# R181X.net
KiCad netlist of a schematic drawn in EAGLE
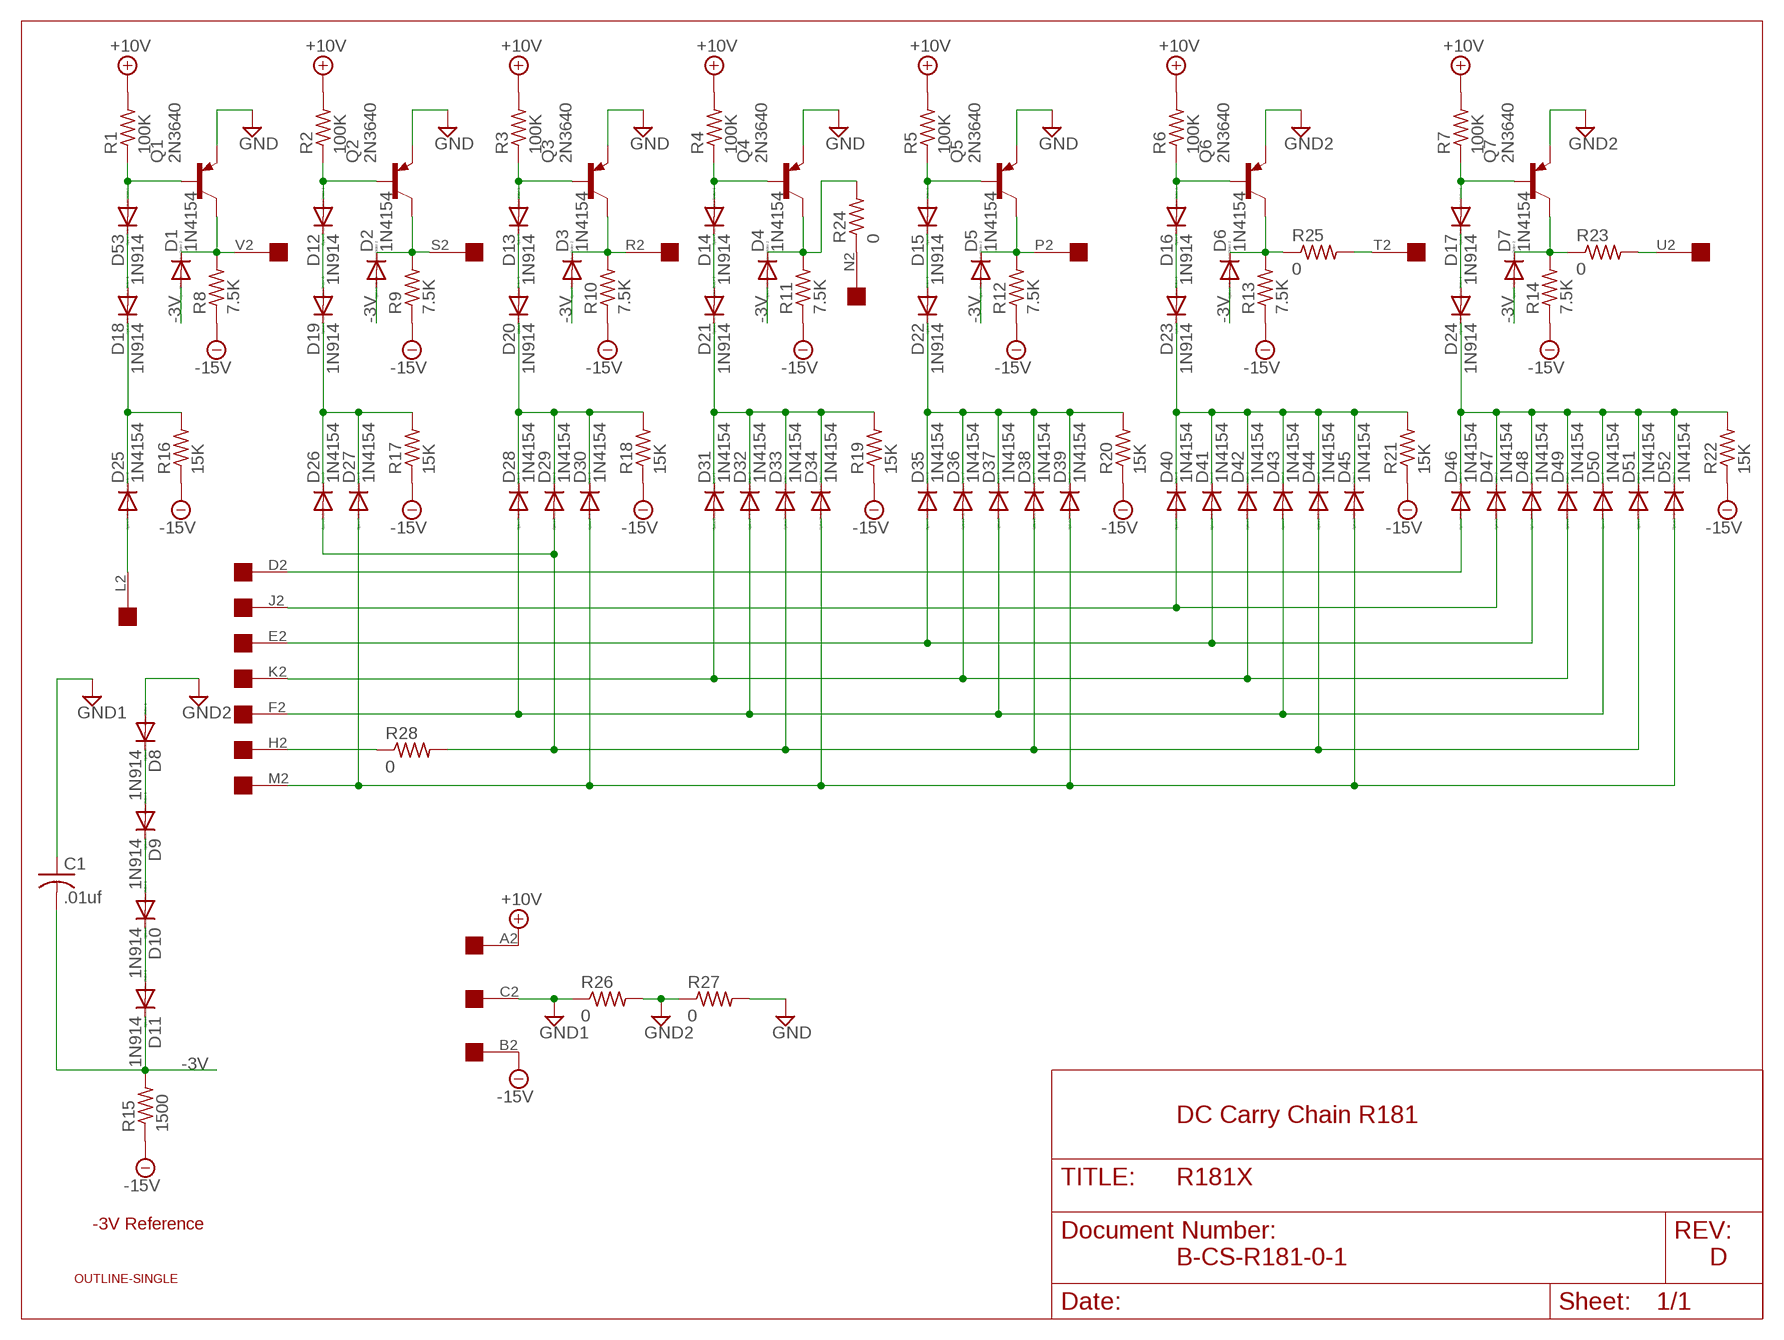
[diagram p0: schematic, sheet 1]

(export (version "E")
  (design (tool "Eeschema 10.0.6"))
  (components
    (comp (ref "C1")
      (value ".01uf")
      (footprint "eagle-import:C050-025X075")
      (libsource (lib "eagle-import") (part "C-US050-025X075"))
    )
    (comp (ref "D1")
      (value "1N4154")
      (footprint "eagle-import:DO35-10")
      (libsource (lib "eagle-import") (part "1N4148DO35-10"))
    )
    (comp (ref "D2")
      (value "1N4154")
      (footprint "eagle-import:DO35-10")
      (libsource (lib "eagle-import") (part "1N4148DO35-10"))
    )
    (comp (ref "D3")
      (value "1N4154")
      (footprint "eagle-import:DO35-10")
      (libsource (lib "eagle-import") (part "1N4148DO35-10"))
    )
    (comp (ref "D4")
      (value "1N4154")
      (footprint "eagle-import:DO35-10")
      (libsource (lib "eagle-import") (part "1N4148DO35-10"))
    )
    (comp (ref "D5")
      (value "1N4154")
      (footprint "eagle-import:DO35-10")
      (libsource (lib "eagle-import") (part "1N4148DO35-10"))
    )
    (comp (ref "D6")
      (value "1N4154")
      (footprint "eagle-import:DO35-10")
      (libsource (lib "eagle-import") (part "1N4148DO35-10"))
    )
    (comp (ref "D7")
      (value "1N4154")
      (footprint "eagle-import:DO35-10")
      (libsource (lib "eagle-import") (part "1N4148DO35-10"))
    )
    (comp (ref "D8")
      (value "1N914")
      (footprint "eagle-import:DO35-10")
      (libsource (lib "eagle-import") (part "1N4148DO35-10"))
    )
    (comp (ref "D9")
      (value "1N914")
      (footprint "eagle-import:DO35-10")
      (libsource (lib "eagle-import") (part "1N4148DO35-10"))
    )
    (comp (ref "D10")
      (value "1N914")
      (footprint "eagle-import:DO35-10")
      (libsource (lib "eagle-import") (part "1N4148DO35-10"))
    )
    (comp (ref "D11")
      (value "1N914")
      (footprint "eagle-import:DO35-10")
      (libsource (lib "eagle-import") (part "1N4148DO35-10"))
    )
    (comp (ref "D12")
      (value "1N914")
      (footprint "eagle-import:DO35-10")
      (libsource (lib "eagle-import") (part "1N4148DO35-10"))
    )
    (comp (ref "D13")
      (value "1N914")
      (footprint "eagle-import:DO35-10")
      (libsource (lib "eagle-import") (part "1N4148DO35-10"))
    )
    (comp (ref "D14")
      (value "1N914")
      (footprint "eagle-import:DO35-10")
      (libsource (lib "eagle-import") (part "1N4148DO35-10"))
    )
    (comp (ref "D15")
      (value "1N914")
      (footprint "eagle-import:DO35-10")
      (libsource (lib "eagle-import") (part "1N4148DO35-10"))
    )
    (comp (ref "D16")
      (value "1N914")
      (footprint "eagle-import:DO35-10")
      (libsource (lib "eagle-import") (part "1N4148DO35-10"))
    )
    (comp (ref "D17")
      (value "1N914")
      (footprint "eagle-import:DO35-10")
      (libsource (lib "eagle-import") (part "1N4148DO35-10"))
    )
    (comp (ref "D18")
      (value "1N914")
      (footprint "eagle-import:DO35-10")
      (libsource (lib "eagle-import") (part "1N4148DO35-10"))
    )
    (comp (ref "D19")
      (value "1N914")
      (footprint "eagle-import:DO35-10")
      (libsource (lib "eagle-import") (part "1N4148DO35-10"))
    )
    (comp (ref "D20")
      (value "1N914")
      (footprint "eagle-import:DO35-10")
      (libsource (lib "eagle-import") (part "1N4148DO35-10"))
    )
    (comp (ref "D21")
      (value "1N914")
      (footprint "eagle-import:DO35-10")
      (libsource (lib "eagle-import") (part "1N4148DO35-10"))
    )
    (comp (ref "D22")
      (value "1N914")
      (footprint "eagle-import:DO35-10")
      (libsource (lib "eagle-import") (part "1N4148DO35-10"))
    )
    (comp (ref "D23")
      (value "1N914")
      (footprint "eagle-import:DO35-10")
      (libsource (lib "eagle-import") (part "1N4148DO35-10"))
    )
    (comp (ref "D24")
      (value "1N914")
      (footprint "eagle-import:DO35-10")
      (libsource (lib "eagle-import") (part "1N4148DO35-10"))
    )
    (comp (ref "D25")
      (value "1N4154")
      (footprint "eagle-import:DO35-10")
      (libsource (lib "eagle-import") (part "1N4148DO35-10"))
    )
    (comp (ref "D26")
      (value "1N4154")
      (footprint "eagle-import:DO35-10")
      (libsource (lib "eagle-import") (part "1N4148DO35-10"))
    )
    (comp (ref "D27")
      (value "1N4154")
      (footprint "eagle-import:DO35-10")
      (libsource (lib "eagle-import") (part "1N4148DO35-10"))
    )
    (comp (ref "D28")
      (value "1N4154")
      (footprint "eagle-import:DO35-10")
      (libsource (lib "eagle-import") (part "1N4148DO35-10"))
    )
    (comp (ref "D29")
      (value "1N4154")
      (footprint "eagle-import:DO35-10")
      (libsource (lib "eagle-import") (part "1N4148DO35-10"))
    )
    (comp (ref "D30")
      (value "1N4154")
      (footprint "eagle-import:DO35-10")
      (libsource (lib "eagle-import") (part "1N4148DO35-10"))
    )
    (comp (ref "D31")
      (value "1N4154")
      (footprint "eagle-import:DO35-10")
      (libsource (lib "eagle-import") (part "1N4148DO35-10"))
    )
    (comp (ref "D32")
      (value "1N4154")
      (footprint "eagle-import:DO35-10")
      (libsource (lib "eagle-import") (part "1N4148DO35-10"))
    )
    (comp (ref "D33")
      (value "1N4154")
      (footprint "eagle-import:DO35-10")
      (libsource (lib "eagle-import") (part "1N4148DO35-10"))
    )
    (comp (ref "D34")
      (value "1N4154")
      (footprint "eagle-import:DO35-10")
      (libsource (lib "eagle-import") (part "1N4148DO35-10"))
    )
    (comp (ref "D35")
      (value "1N4154")
      (footprint "eagle-import:DO35-10")
      (libsource (lib "eagle-import") (part "1N4148DO35-10"))
    )
    (comp (ref "D36")
      (value "1N4154")
      (footprint "eagle-import:DO35-10")
      (libsource (lib "eagle-import") (part "1N4148DO35-10"))
    )
    (comp (ref "D37")
      (value "1N4154")
      (footprint "eagle-import:DO35-10")
      (libsource (lib "eagle-import") (part "1N4148DO35-10"))
    )
    (comp (ref "D38")
      (value "1N4154")
      (footprint "eagle-import:DO35-10")
      (libsource (lib "eagle-import") (part "1N4148DO35-10"))
    )
    (comp (ref "D39")
      (value "1N4154")
      (footprint "eagle-import:DO35-10")
      (libsource (lib "eagle-import") (part "1N4148DO35-10"))
    )
    (comp (ref "D40")
      (value "1N4154")
      (footprint "eagle-import:DO35-10")
      (libsource (lib "eagle-import") (part "1N4148DO35-10"))
    )
    (comp (ref "D41")
      (value "1N4154")
      (footprint "eagle-import:DO35-10")
      (libsource (lib "eagle-import") (part "1N4148DO35-10"))
    )
    (comp (ref "D42")
      (value "1N4154")
      (footprint "eagle-import:DO35-10")
      (libsource (lib "eagle-import") (part "1N4148DO35-10"))
    )
    (comp (ref "D43")
      (value "1N4154")
      (footprint "eagle-import:DO35-10")
      (libsource (lib "eagle-import") (part "1N4148DO35-10"))
    )
    (comp (ref "D44")
      (value "1N4154")
      (footprint "eagle-import:DO35-10")
      (libsource (lib "eagle-import") (part "1N4148DO35-10"))
    )
    (comp (ref "D45")
      (value "1N4154")
      (footprint "eagle-import:DO35-10")
      (libsource (lib "eagle-import") (part "1N4148DO35-10"))
    )
    (comp (ref "D46")
      (value "1N4154")
      (footprint "eagle-import:DO35-10")
      (libsource (lib "eagle-import") (part "1N4148DO35-10"))
    )
    (comp (ref "D47")
      (value "1N4154")
      (footprint "eagle-import:DO35-10")
      (libsource (lib "eagle-import") (part "1N4148DO35-10"))
    )
    (comp (ref "D48")
      (value "1N4154")
      (footprint "eagle-import:DO35-10")
      (libsource (lib "eagle-import") (part "1N4148DO35-10"))
    )
    (comp (ref "D49")
      (value "1N4154")
      (footprint "eagle-import:DO35-10")
      (libsource (lib "eagle-import") (part "1N4148DO35-10"))
    )
    (comp (ref "D50")
      (value "1N4154")
      (footprint "eagle-import:DO35-10")
      (libsource (lib "eagle-import") (part "1N4148DO35-10"))
    )
    (comp (ref "D51")
      (value "1N4154")
      (footprint "eagle-import:DO35-10")
      (libsource (lib "eagle-import") (part "1N4148DO35-10"))
    )
    (comp (ref "D52")
      (value "1N4154")
      (footprint "eagle-import:DO35-10")
      (libsource (lib "eagle-import") (part "1N4148DO35-10"))
    )
    (comp (ref "D53")
      (value "1N914")
      (footprint "eagle-import:DO35-10")
      (libsource (lib "eagle-import") (part "1N4148DO35-10"))
    )
    (comp (ref "Q1")
      (value "2N3640")
      (footprint "eagle-import:TO39")
      (libsource (lib "eagle-import") (part "2N3637"))
    )
    (comp (ref "Q2")
      (value "2N3640")
      (footprint "eagle-import:TO39")
      (libsource (lib "eagle-import") (part "2N3637"))
    )
    (comp (ref "Q3")
      (value "2N3640")
      (footprint "eagle-import:TO39")
      (libsource (lib "eagle-import") (part "2N3637"))
    )
    (comp (ref "Q4")
      (value "2N3640")
      (footprint "eagle-import:TO39")
      (libsource (lib "eagle-import") (part "2N3637"))
    )
    (comp (ref "Q5")
      (value "2N3640")
      (footprint "eagle-import:TO39")
      (libsource (lib "eagle-import") (part "2N3637"))
    )
    (comp (ref "Q6")
      (value "2N3640")
      (footprint "eagle-import:TO39")
      (libsource (lib "eagle-import") (part "2N3637"))
    )
    (comp (ref "Q7")
      (value "2N3640")
      (footprint "eagle-import:TO39")
      (libsource (lib "eagle-import") (part "2N3637"))
    )
    (comp (ref "R1")
      (value "100K")
      (footprint "eagle-import:0207_10")
      (libsource (lib "eagle-import") (part "R-US_0207/10"))
    )
    (comp (ref "R2")
      (value "100K")
      (footprint "eagle-import:0207_10")
      (libsource (lib "eagle-import") (part "R-US_0207/10"))
    )
    (comp (ref "R3")
      (value "100K")
      (footprint "eagle-import:0207_10")
      (libsource (lib "eagle-import") (part "R-US_0207/10"))
    )
    (comp (ref "R4")
      (value "100K")
      (footprint "eagle-import:0207_10")
      (libsource (lib "eagle-import") (part "R-US_0207/10"))
    )
    (comp (ref "R5")
      (value "100K")
      (footprint "eagle-import:0207_10")
      (libsource (lib "eagle-import") (part "R-US_0207/10"))
    )
    (comp (ref "R6")
      (value "100K")
      (footprint "eagle-import:0207_10")
      (libsource (lib "eagle-import") (part "R-US_0207/10"))
    )
    (comp (ref "R7")
      (value "100K")
      (footprint "eagle-import:0207_10")
      (libsource (lib "eagle-import") (part "R-US_0207/10"))
    )
    (comp (ref "R8")
      (value "7.5K")
      (footprint "eagle-import:0207_10")
      (libsource (lib "eagle-import") (part "R-US_0207/10"))
    )
    (comp (ref "R9")
      (value "7.5K")
      (footprint "eagle-import:0207_10")
      (libsource (lib "eagle-import") (part "R-US_0207/10"))
    )
    (comp (ref "R10")
      (value "7.5K")
      (footprint "eagle-import:0207_10")
      (libsource (lib "eagle-import") (part "R-US_0207/10"))
    )
    (comp (ref "R11")
      (value "7.5K")
      (footprint "eagle-import:0207_10")
      (libsource (lib "eagle-import") (part "R-US_0207/10"))
    )
    (comp (ref "R12")
      (value "7.5K")
      (footprint "eagle-import:0207_10")
      (libsource (lib "eagle-import") (part "R-US_0207/10"))
    )
    (comp (ref "R13")
      (value "7.5K")
      (footprint "eagle-import:0207_10")
      (libsource (lib "eagle-import") (part "R-US_0207/10"))
    )
    (comp (ref "R14")
      (value "7.5K")
      (footprint "eagle-import:0207_10")
      (libsource (lib "eagle-import") (part "R-US_0207/10"))
    )
    (comp (ref "R15")
      (value "1500")
      (footprint "eagle-import:0207_10")
      (libsource (lib "eagle-import") (part "R-US_0207/10"))
    )
    (comp (ref "R16")
      (value "15K")
      (footprint "eagle-import:0207_10")
      (libsource (lib "eagle-import") (part "R-US_0207/10"))
    )
    (comp (ref "R17")
      (value "15K")
      (footprint "eagle-import:0207_10")
      (libsource (lib "eagle-import") (part "R-US_0207/10"))
    )
    (comp (ref "R18")
      (value "15K")
      (footprint "eagle-import:0207_10")
      (libsource (lib "eagle-import") (part "R-US_0207/10"))
    )
    (comp (ref "R19")
      (value "15K")
      (footprint "eagle-import:0207_10")
      (libsource (lib "eagle-import") (part "R-US_0207/10"))
    )
    (comp (ref "R20")
      (value "15K")
      (footprint "eagle-import:0207_10")
      (libsource (lib "eagle-import") (part "R-US_0207/10"))
    )
    (comp (ref "R21")
      (value "15K")
      (footprint "eagle-import:0207_10")
      (libsource (lib "eagle-import") (part "R-US_0207/10"))
    )
    (comp (ref "R22")
      (value "15K")
      (footprint "eagle-import:0207_10")
      (libsource (lib "eagle-import") (part "R-US_0207/10"))
    )
    (comp (ref "R23")
      (value "0")
      (footprint "eagle-import:0207_10")
      (libsource (lib "eagle-import") (part "R-US_0207/10"))
    )
    (comp (ref "R24")
      (value "0")
      (footprint "eagle-import:0207_10")
      (libsource (lib "eagle-import") (part "R-US_0207/10"))
    )
    (comp (ref "R25")
      (value "0")
      (footprint "eagle-import:0207_10")
      (libsource (lib "eagle-import") (part "R-US_0207/10"))
    )
    (comp (ref "R26")
      (value "0")
      (footprint "eagle-import:0207_10")
      (libsource (lib "eagle-import") (part "R-US_0207/10"))
    )
    (comp (ref "R27")
      (value "0")
      (footprint "eagle-import:0207_10")
      (libsource (lib "eagle-import") (part "R-US_0207/10"))
    )
    (comp (ref "R28")
      (value "0")
      (footprint "eagle-import:0207_10")
      (libsource (lib "eagle-import") (part "R-US_0207/10"))
    )
    (comp (ref "U$1")
      (value "OUTLINE-SINGLE")
      (footprint "eagle-import:SINGLE")
      (libsource (lib "eagle-import") (part "OUTLINE-SINGLE"))
    )
    (comp (ref "U$2")
      (value "EDGE-1")
      (footprint "eagle-import:EDGE-CON1")
      (libsource (lib "eagle-import") (part "EDGE-1"))
    )
  )
  (nets
    (net (code "1") (name "+10V") (class "Default")
      (node (ref "R1") (pin "2") (pinfunction "2_2") (pintype "passive"))
      (node (ref "R2") (pin "2") (pinfunction "2_2") (pintype "passive"))
      (node (ref "R3") (pin "2") (pinfunction "2_2") (pintype "passive"))
      (node (ref "R4") (pin "2") (pinfunction "2_2") (pintype "passive"))
      (node (ref "R5") (pin "2") (pinfunction "2_2") (pintype "passive"))
      (node (ref "R6") (pin "2") (pinfunction "2_2") (pintype "passive"))
      (node (ref "R7") (pin "2") (pinfunction "2_2") (pintype "passive"))
      (node (ref "U$2") (pin "A2") (pinfunction "1_A2") (pintype "bidirectional"))
    )
    (net (code "2") (name "-15V") (class "Default")
      (node (ref "R10") (pin "1") (pinfunction "1_1") (pintype "passive"))
      (node (ref "R11") (pin "1") (pinfunction "1_1") (pintype "passive"))
      (node (ref "R12") (pin "1") (pinfunction "1_1") (pintype "passive"))
      (node (ref "R13") (pin "1") (pinfunction "1_1") (pintype "passive"))
      (node (ref "R14") (pin "1") (pinfunction "1_1") (pintype "passive"))
      (node (ref "R15") (pin "1") (pinfunction "1_1") (pintype "passive"))
      (node (ref "R16") (pin "1") (pinfunction "1_1") (pintype "passive"))
      (node (ref "R17") (pin "1") (pinfunction "1_1") (pintype "passive"))
      (node (ref "R18") (pin "1") (pinfunction "1_1") (pintype "passive"))
      (node (ref "R19") (pin "1") (pinfunction "1_1") (pintype "passive"))
      (node (ref "R20") (pin "1") (pinfunction "1_1") (pintype "passive"))
      (node (ref "R21") (pin "1") (pinfunction "1_1") (pintype "passive"))
      (node (ref "R22") (pin "1") (pinfunction "1_1") (pintype "passive"))
      (node (ref "R8") (pin "1") (pinfunction "1_1") (pintype "passive"))
      (node (ref "R9") (pin "1") (pinfunction "1_1") (pintype "passive"))
      (node (ref "U$2") (pin "B2") (pinfunction "1_B2") (pintype "bidirectional"))
    )
    (net (code "3") (name "/-3V") (class "Default")
      (node (ref "C1") (pin "2") (pinfunction "2_2") (pintype "passive"))
      (node (ref "D1") (pin "A") (pinfunction "A_A") (pintype "passive"))
      (node (ref "D11") (pin "C") (pinfunction "C_C") (pintype "passive"))
      (node (ref "D2") (pin "A") (pinfunction "A_A") (pintype "passive"))
      (node (ref "D3") (pin "A") (pinfunction "A_A") (pintype "passive"))
      (node (ref "D4") (pin "A") (pinfunction "A_A") (pintype "passive"))
      (node (ref "D5") (pin "A") (pinfunction "A_A") (pintype "passive"))
      (node (ref "D6") (pin "A") (pinfunction "A_A") (pintype "passive"))
      (node (ref "D7") (pin "A") (pinfunction "A_A") (pintype "passive"))
      (node (ref "R15") (pin "2") (pinfunction "2_2") (pintype "passive"))
    )
    (net (code "4") (name "GND") (class "Default")
      (node (ref "Q1") (pin "1") (pinfunction "E_1") (pintype "passive"))
      (node (ref "Q2") (pin "1") (pinfunction "E_1") (pintype "passive"))
      (node (ref "Q3") (pin "1") (pinfunction "E_1") (pintype "passive"))
      (node (ref "Q4") (pin "1") (pinfunction "E_1") (pintype "passive"))
      (node (ref "Q5") (pin "1") (pinfunction "E_1") (pintype "passive"))
      (node (ref "R27") (pin "2") (pinfunction "2_2") (pintype "passive"))
    )
    (net (code "5") (name "GND1") (class "Default")
      (node (ref "C1") (pin "1") (pinfunction "1_1") (pintype "passive"))
      (node (ref "R26") (pin "1") (pinfunction "1_1") (pintype "passive"))
      (node (ref "U$2") (pin "C2") (pinfunction "1_C2") (pintype "bidirectional"))
    )
    (net (code "6") (name "GND2") (class "Default")
      (node (ref "D8") (pin "A") (pinfunction "A_A") (pintype "passive"))
      (node (ref "Q6") (pin "1") (pinfunction "E_1") (pintype "passive"))
      (node (ref "Q7") (pin "1") (pinfunction "E_1") (pintype "passive"))
      (node (ref "R26") (pin "2") (pinfunction "2_2") (pintype "passive"))
      (node (ref "R27") (pin "1") (pinfunction "1_1") (pintype "passive"))
    )
    (net (code "7") (name "Net-(D8-PadC)") (class "Default")
      (node (ref "D8") (pin "C") (pinfunction "C_C") (pintype "passive"))
      (node (ref "D9") (pin "A") (pinfunction "A_A") (pintype "passive"))
    )
    (net (code "8") (name "Net-(D10-PadA)") (class "Default")
      (node (ref "D10") (pin "A") (pinfunction "A_A") (pintype "passive"))
      (node (ref "D9") (pin "C") (pinfunction "C_C") (pintype "passive"))
    )
    (net (code "9") (name "Net-(D10-PadC)") (class "Default")
      (node (ref "D10") (pin "C") (pinfunction "C_C") (pintype "passive"))
      (node (ref "D11") (pin "A") (pinfunction "A_A") (pintype "passive"))
    )
    (net (code "10") (name "Net-(D12-PadC)") (class "Default")
      (node (ref "D12") (pin "C") (pinfunction "C_C") (pintype "passive"))
      (node (ref "D19") (pin "A") (pinfunction "A_A") (pintype "passive"))
    )
    (net (code "11") (name "Net-(D13-PadC)") (class "Default")
      (node (ref "D13") (pin "C") (pinfunction "C_C") (pintype "passive"))
      (node (ref "D20") (pin "A") (pinfunction "A_A") (pintype "passive"))
    )
    (net (code "12") (name "Net-(D14-PadC)") (class "Default")
      (node (ref "D14") (pin "C") (pinfunction "C_C") (pintype "passive"))
      (node (ref "D21") (pin "A") (pinfunction "A_A") (pintype "passive"))
    )
    (net (code "13") (name "Net-(D15-PadC)") (class "Default")
      (node (ref "D15") (pin "C") (pinfunction "C_C") (pintype "passive"))
      (node (ref "D22") (pin "A") (pinfunction "A_A") (pintype "passive"))
    )
    (net (code "14") (name "Net-(D16-PadC)") (class "Default")
      (node (ref "D16") (pin "C") (pinfunction "C_C") (pintype "passive"))
      (node (ref "D23") (pin "A") (pinfunction "A_A") (pintype "passive"))
    )
    (net (code "15") (name "Net-(D17-PadC)") (class "Default")
      (node (ref "D17") (pin "C") (pinfunction "C_C") (pintype "passive"))
      (node (ref "D24") (pin "A") (pinfunction "A_A") (pintype "passive"))
    )
    (net (code "16") (name "Net-(D18-PadA)") (class "Default")
      (node (ref "D18") (pin "A") (pinfunction "A_A") (pintype "passive"))
      (node (ref "D53") (pin "C") (pinfunction "C_C") (pintype "passive"))
    )
    (net (code "17") (name "Net-(D18-PadC)") (class "Default")
      (node (ref "D18") (pin "C") (pinfunction "C_C") (pintype "passive"))
      (node (ref "D25") (pin "C") (pinfunction "C_C") (pintype "passive"))
      (node (ref "R16") (pin "2") (pinfunction "2_2") (pintype "passive"))
    )
    (net (code "18") (name "Net-(D19-PadC)") (class "Default")
      (node (ref "D19") (pin "C") (pinfunction "C_C") (pintype "passive"))
      (node (ref "D26") (pin "C") (pinfunction "C_C") (pintype "passive"))
      (node (ref "D27") (pin "C") (pinfunction "C_C") (pintype "passive"))
      (node (ref "R17") (pin "2") (pinfunction "2_2") (pintype "passive"))
    )
    (net (code "19") (name "Net-(D20-PadC)") (class "Default")
      (node (ref "D20") (pin "C") (pinfunction "C_C") (pintype "passive"))
      (node (ref "D28") (pin "C") (pinfunction "C_C") (pintype "passive"))
      (node (ref "D29") (pin "C") (pinfunction "C_C") (pintype "passive"))
      (node (ref "D30") (pin "C") (pinfunction "C_C") (pintype "passive"))
      (node (ref "R18") (pin "2") (pinfunction "2_2") (pintype "passive"))
    )
    (net (code "20") (name "Net-(D21-PadC)") (class "Default")
      (node (ref "D21") (pin "C") (pinfunction "C_C") (pintype "passive"))
      (node (ref "D31") (pin "C") (pinfunction "C_C") (pintype "passive"))
      (node (ref "D32") (pin "C") (pinfunction "C_C") (pintype "passive"))
      (node (ref "D33") (pin "C") (pinfunction "C_C") (pintype "passive"))
      (node (ref "D34") (pin "C") (pinfunction "C_C") (pintype "passive"))
      (node (ref "R19") (pin "2") (pinfunction "2_2") (pintype "passive"))
    )
    (net (code "21") (name "Net-(D22-PadC)") (class "Default")
      (node (ref "D22") (pin "C") (pinfunction "C_C") (pintype "passive"))
      (node (ref "D35") (pin "C") (pinfunction "C_C") (pintype "passive"))
      (node (ref "D36") (pin "C") (pinfunction "C_C") (pintype "passive"))
      (node (ref "D37") (pin "C") (pinfunction "C_C") (pintype "passive"))
      (node (ref "D38") (pin "C") (pinfunction "C_C") (pintype "passive"))
      (node (ref "D39") (pin "C") (pinfunction "C_C") (pintype "passive"))
      (node (ref "R20") (pin "2") (pinfunction "2_2") (pintype "passive"))
    )
    (net (code "22") (name "Net-(D23-PadC)") (class "Default")
      (node (ref "D23") (pin "C") (pinfunction "C_C") (pintype "passive"))
      (node (ref "D40") (pin "C") (pinfunction "C_C") (pintype "passive"))
      (node (ref "D41") (pin "C") (pinfunction "C_C") (pintype "passive"))
      (node (ref "D42") (pin "C") (pinfunction "C_C") (pintype "passive"))
      (node (ref "D43") (pin "C") (pinfunction "C_C") (pintype "passive"))
      (node (ref "D44") (pin "C") (pinfunction "C_C") (pintype "passive"))
      (node (ref "D45") (pin "C") (pinfunction "C_C") (pintype "passive"))
      (node (ref "R21") (pin "2") (pinfunction "2_2") (pintype "passive"))
    )
    (net (code "23") (name "Net-(D24-PadC)") (class "Default")
      (node (ref "D24") (pin "C") (pinfunction "C_C") (pintype "passive"))
      (node (ref "D46") (pin "C") (pinfunction "C_C") (pintype "passive"))
      (node (ref "D47") (pin "C") (pinfunction "C_C") (pintype "passive"))
      (node (ref "D48") (pin "C") (pinfunction "C_C") (pintype "passive"))
      (node (ref "D49") (pin "C") (pinfunction "C_C") (pintype "passive"))
      (node (ref "D50") (pin "C") (pinfunction "C_C") (pintype "passive"))
      (node (ref "D51") (pin "C") (pinfunction "C_C") (pintype "passive"))
      (node (ref "D52") (pin "C") (pinfunction "C_C") (pintype "passive"))
      (node (ref "R22") (pin "2") (pinfunction "2_2") (pintype "passive"))
    )
    (net (code "24") (name "Net-(D26-PadA)") (class "Default")
      (node (ref "D26") (pin "A") (pinfunction "A_A") (pintype "passive"))
      (node (ref "D29") (pin "A") (pinfunction "A_A") (pintype "passive"))
      (node (ref "D33") (pin "A") (pinfunction "A_A") (pintype "passive"))
      (node (ref "D38") (pin "A") (pinfunction "A_A") (pintype "passive"))
      (node (ref "D44") (pin "A") (pinfunction "A_A") (pintype "passive"))
      (node (ref "D51") (pin "A") (pinfunction "A_A") (pintype "passive"))
      (node (ref "R28") (pin "2") (pinfunction "2_2") (pintype "passive"))
    )
    (net (code "25") (name "Net-(Q1-B)") (class "Default")
      (node (ref "D53") (pin "A") (pinfunction "A_A") (pintype "passive"))
      (node (ref "Q1") (pin "2") (pinfunction "B_2") (pintype "passive"))
      (node (ref "R1") (pin "1") (pinfunction "1_1") (pintype "passive"))
    )
    (net (code "26") (name "Net-(Q1-C)") (class "Default")
      (node (ref "D1") (pin "C") (pinfunction "C_C") (pintype "passive"))
      (node (ref "Q1") (pin "3") (pinfunction "C_3") (pintype "passive"))
      (node (ref "R8") (pin "2") (pinfunction "2_2") (pintype "passive"))
      (node (ref "U$2") (pin "V2") (pinfunction "1_V2") (pintype "bidirectional"))
    )
    (net (code "27") (name "Net-(Q2-B)") (class "Default")
      (node (ref "D12") (pin "A") (pinfunction "A_A") (pintype "passive"))
      (node (ref "Q2") (pin "2") (pinfunction "B_2") (pintype "passive"))
      (node (ref "R2") (pin "1") (pinfunction "1_1") (pintype "passive"))
    )
    (net (code "28") (name "Net-(Q2-C)") (class "Default")
      (node (ref "D2") (pin "C") (pinfunction "C_C") (pintype "passive"))
      (node (ref "Q2") (pin "3") (pinfunction "C_3") (pintype "passive"))
      (node (ref "R9") (pin "2") (pinfunction "2_2") (pintype "passive"))
      (node (ref "U$2") (pin "S2") (pinfunction "1_S2") (pintype "bidirectional"))
    )
    (net (code "29") (name "Net-(Q3-B)") (class "Default")
      (node (ref "D13") (pin "A") (pinfunction "A_A") (pintype "passive"))
      (node (ref "Q3") (pin "2") (pinfunction "B_2") (pintype "passive"))
      (node (ref "R3") (pin "1") (pinfunction "1_1") (pintype "passive"))
    )
    (net (code "30") (name "Net-(Q3-C)") (class "Default")
      (node (ref "D3") (pin "C") (pinfunction "C_C") (pintype "passive"))
      (node (ref "Q3") (pin "3") (pinfunction "C_3") (pintype "passive"))
      (node (ref "R10") (pin "2") (pinfunction "2_2") (pintype "passive"))
      (node (ref "U$2") (pin "R2") (pinfunction "1_R2") (pintype "bidirectional"))
    )
    (net (code "31") (name "Net-(Q4-B)") (class "Default")
      (node (ref "D14") (pin "A") (pinfunction "A_A") (pintype "passive"))
      (node (ref "Q4") (pin "2") (pinfunction "B_2") (pintype "passive"))
      (node (ref "R4") (pin "1") (pinfunction "1_1") (pintype "passive"))
    )
    (net (code "32") (name "Net-(Q4-C)") (class "Default")
      (node (ref "D4") (pin "C") (pinfunction "C_C") (pintype "passive"))
      (node (ref "Q4") (pin "3") (pinfunction "C_3") (pintype "passive"))
      (node (ref "R11") (pin "2") (pinfunction "2_2") (pintype "passive"))
      (node (ref "R24") (pin "2") (pinfunction "2_2") (pintype "passive"))
    )
    (net (code "33") (name "Net-(Q5-B)") (class "Default")
      (node (ref "D15") (pin "A") (pinfunction "A_A") (pintype "passive"))
      (node (ref "Q5") (pin "2") (pinfunction "B_2") (pintype "passive"))
      (node (ref "R5") (pin "1") (pinfunction "1_1") (pintype "passive"))
    )
    (net (code "34") (name "Net-(Q5-C)") (class "Default")
      (node (ref "D5") (pin "C") (pinfunction "C_C") (pintype "passive"))
      (node (ref "Q5") (pin "3") (pinfunction "C_3") (pintype "passive"))
      (node (ref "R12") (pin "2") (pinfunction "2_2") (pintype "passive"))
      (node (ref "U$2") (pin "P2") (pinfunction "1_P2") (pintype "bidirectional"))
    )
    (net (code "35") (name "Net-(Q6-B)") (class "Default")
      (node (ref "D16") (pin "A") (pinfunction "A_A") (pintype "passive"))
      (node (ref "Q6") (pin "2") (pinfunction "B_2") (pintype "passive"))
      (node (ref "R6") (pin "1") (pinfunction "1_1") (pintype "passive"))
    )
    (net (code "36") (name "Net-(Q6-C)") (class "Default")
      (node (ref "D6") (pin "C") (pinfunction "C_C") (pintype "passive"))
      (node (ref "Q6") (pin "3") (pinfunction "C_3") (pintype "passive"))
      (node (ref "R13") (pin "2") (pinfunction "2_2") (pintype "passive"))
      (node (ref "R25") (pin "1") (pinfunction "1_1") (pintype "passive"))
    )
    (net (code "37") (name "Net-(Q7-B)") (class "Default")
      (node (ref "D17") (pin "A") (pinfunction "A_A") (pintype "passive"))
      (node (ref "Q7") (pin "2") (pinfunction "B_2") (pintype "passive"))
      (node (ref "R7") (pin "1") (pinfunction "1_1") (pintype "passive"))
    )
    (net (code "38") (name "Net-(Q7-C)") (class "Default")
      (node (ref "D7") (pin "C") (pinfunction "C_C") (pintype "passive"))
      (node (ref "Q7") (pin "3") (pinfunction "C_3") (pintype "passive"))
      (node (ref "R14") (pin "2") (pinfunction "2_2") (pintype "passive"))
      (node (ref "R23") (pin "1") (pinfunction "1_1") (pintype "passive"))
    )
    (net (code "39") (name "Net-(U$2D-1)") (class "Default")
      (node (ref "D46") (pin "A") (pinfunction "A_A") (pintype "passive"))
      (node (ref "U$2") (pin "D2") (pinfunction "1_D2") (pintype "bidirectional"))
    )
    (net (code "40") (name "Net-(U$2E-1)") (class "Default")
      (node (ref "D35") (pin "A") (pinfunction "A_A") (pintype "passive"))
      (node (ref "D41") (pin "A") (pinfunction "A_A") (pintype "passive"))
      (node (ref "D48") (pin "A") (pinfunction "A_A") (pintype "passive"))
      (node (ref "U$2") (pin "E2") (pinfunction "1_E2") (pintype "bidirectional"))
    )
    (net (code "41") (name "Net-(U$2F-1)") (class "Default")
      (node (ref "D28") (pin "A") (pinfunction "A_A") (pintype "passive"))
      (node (ref "D32") (pin "A") (pinfunction "A_A") (pintype "passive"))
      (node (ref "D37") (pin "A") (pinfunction "A_A") (pintype "passive"))
      (node (ref "D43") (pin "A") (pinfunction "A_A") (pintype "passive"))
      (node (ref "D50") (pin "A") (pinfunction "A_A") (pintype "passive"))
      (node (ref "U$2") (pin "F2") (pinfunction "1_F2") (pintype "bidirectional"))
    )
    (net (code "42") (name "Net-(U$2G-1)") (class "Default")
      (node (ref "R28") (pin "1") (pinfunction "1_1") (pintype "passive"))
      (node (ref "U$2") (pin "H2") (pinfunction "1_H2") (pintype "bidirectional"))
    )
    (net (code "43") (name "Net-(U$2H-1)") (class "Default")
      (node (ref "D40") (pin "A") (pinfunction "A_A") (pintype "passive"))
      (node (ref "D47") (pin "A") (pinfunction "A_A") (pintype "passive"))
      (node (ref "U$2") (pin "J2") (pinfunction "1_J2") (pintype "bidirectional"))
    )
    (net (code "44") (name "Net-(U$2I-1)") (class "Default")
      (node (ref "D31") (pin "A") (pinfunction "A_A") (pintype "passive"))
      (node (ref "D36") (pin "A") (pinfunction "A_A") (pintype "passive"))
      (node (ref "D42") (pin "A") (pinfunction "A_A") (pintype "passive"))
      (node (ref "D49") (pin "A") (pinfunction "A_A") (pintype "passive"))
      (node (ref "U$2") (pin "K2") (pinfunction "1_K2") (pintype "bidirectional"))
    )
    (net (code "45") (name "Net-(U$2J-1)") (class "Default")
      (node (ref "D25") (pin "A") (pinfunction "A_A") (pintype "passive"))
      (node (ref "U$2") (pin "L2") (pinfunction "1_L2") (pintype "bidirectional"))
    )
    (net (code "46") (name "Net-(U$2K-1)") (class "Default")
      (node (ref "D27") (pin "A") (pinfunction "A_A") (pintype "passive"))
      (node (ref "D30") (pin "A") (pinfunction "A_A") (pintype "passive"))
      (node (ref "D34") (pin "A") (pinfunction "A_A") (pintype "passive"))
      (node (ref "D39") (pin "A") (pinfunction "A_A") (pintype "passive"))
      (node (ref "D45") (pin "A") (pinfunction "A_A") (pintype "passive"))
      (node (ref "D52") (pin "A") (pinfunction "A_A") (pintype "passive"))
      (node (ref "U$2") (pin "M2") (pinfunction "1_M2") (pintype "bidirectional"))
    )
    (net (code "47") (name "Net-(U$2L-1)") (class "Default")
      (node (ref "R24") (pin "1") (pinfunction "1_1") (pintype "passive"))
      (node (ref "U$2") (pin "N2") (pinfunction "1_N2") (pintype "bidirectional"))
    )
    (net (code "48") (name "Net-(U$2P-1)") (class "Default")
      (node (ref "R25") (pin "2") (pinfunction "2_2") (pintype "passive"))
      (node (ref "U$2") (pin "T2") (pinfunction "1_T2") (pintype "bidirectional"))
    )
    (net (code "49") (name "Net-(U$2Q-1)") (class "Default")
      (node (ref "R23") (pin "2") (pinfunction "2_2") (pintype "passive"))
      (node (ref "U$2") (pin "U2") (pinfunction "1_U2") (pintype "bidirectional"))
    )
  )
)
